# top_board.net
KiCad netlist of a schematic drawn in EAGLE
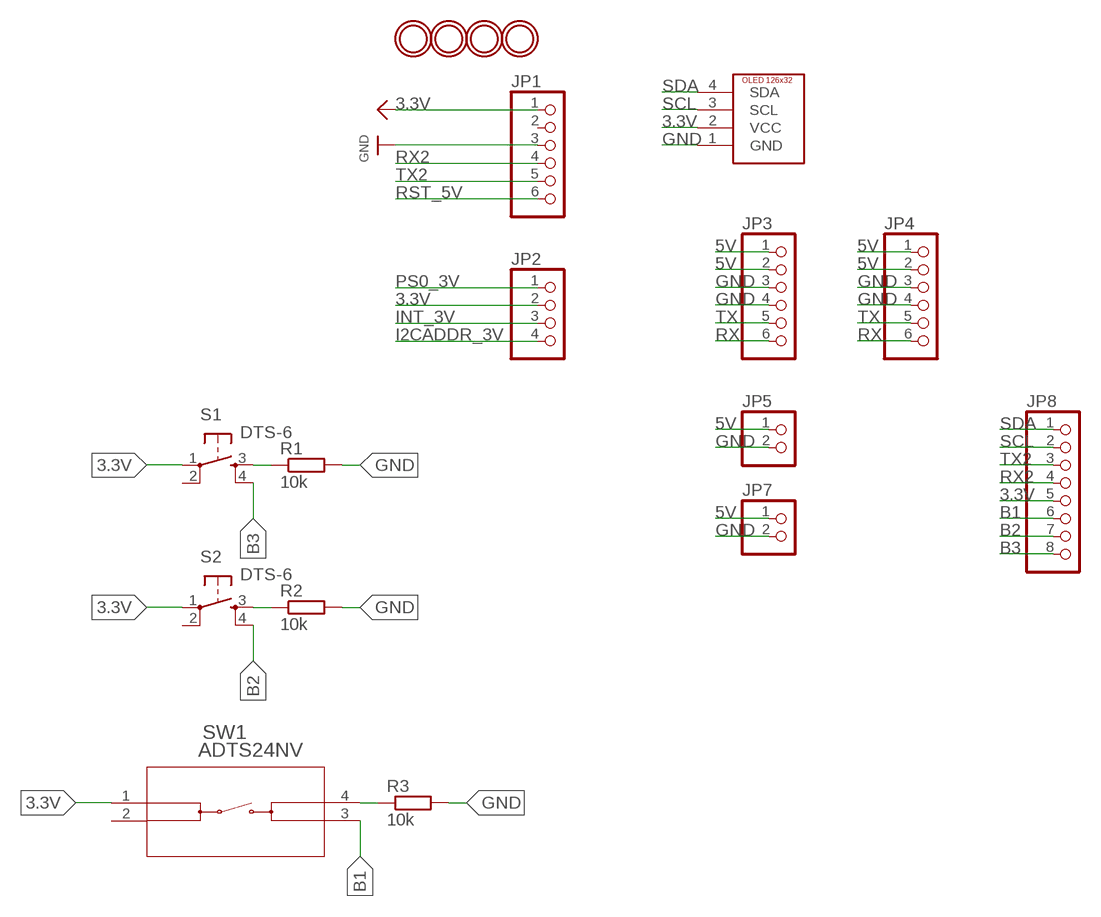
[diagram p0: schematic, sheet 1]

(export (version "E")
  (design (tool "Eeschema 10.0.6"))
  (components
    (comp (ref "JP1")
      (value "HEADER-1X676MIL")
      (footprint "eagle-import:1X06_ROUND_76")
      (libsource (lib "eagle-import") (part "HEADER-1X676MIL"))
    )
    (comp (ref "JP2")
      (value "HEADER-1X476MIL")
      (footprint "eagle-import:1X04_ROUND_76")
      (libsource (lib "eagle-import") (part "HEADER-1X476MIL"))
    )
    (comp (ref "JP3")
      (value "PINHD-1X6")
      (footprint "eagle-import:1X06")
      (libsource (lib "eagle-import") (part "PINHD-1X6"))
    )
    (comp (ref "JP4")
      (value "PINHD-1X6")
      (footprint "eagle-import:1X06")
      (libsource (lib "eagle-import") (part "PINHD-1X6"))
    )
    (comp (ref "JP5")
      (value "PINHD-1X2")
      (footprint "eagle-import:1X02")
      (libsource (lib "eagle-import") (part "PINHD-1X2"))
    )
    (comp (ref "JP7")
      (value "PINHD-1X2")
      (footprint "eagle-import:1X02")
      (libsource (lib "eagle-import") (part "PINHD-1X2"))
    )
    (comp (ref "JP8")
      (value "PINHD-1X8")
      (footprint "eagle-import:1X08")
      (libsource (lib "eagle-import") (part "PINHD-1X8"))
    )
    (comp (ref "R1")
      (value "10k")
      (footprint "eagle-import:R0603")
      (libsource (lib "eagle-import") (part "R-EU_R0603"))
    )
    (comp (ref "R2")
      (value "10k")
      (footprint "eagle-import:R0603")
      (libsource (lib "eagle-import") (part "R-EU_R0603"))
    )
    (comp (ref "R3")
      (value "10k")
      (footprint "eagle-import:R0603")
      (libsource (lib "eagle-import") (part "R-EU_R0603"))
    )
    (comp (ref "S1")
      (value "DTS-6")
      (footprint "eagle-import:DTS-6")
      (libsource (lib "eagle-import") (part "DTS-6"))
    )
    (comp (ref "S2")
      (value "DTS-6")
      (footprint "eagle-import:DTS-6")
      (libsource (lib "eagle-import") (part "DTS-6"))
    )
    (comp (ref "SW1")
      (value "ADTS24NV")
      (footprint "eagle-import:ADTS24_V_APM")
      (fields (field (name "COPYRIGHT") "Copyright (C) 2023 Ultra Librarian. All rights reserved."))
      (libsource (lib "eagle-import") (part "ADTS24NV"))
    )
    (comp (ref "U$1")
      (value "OLED126X32THROUGH_HOLE")
      (footprint "eagle-import:OLED128X64")
      (libsource (lib "eagle-import") (part "OLED126X32THROUGH_HOLE"))
    )
    (comp (ref "U$29")
      (value "MOUNTINGHOLE2.5_THICK")
      (footprint "eagle-import:MOUNTINGHOLE_2.5_PLATED_THICK")
      (libsource (lib "eagle-import") (part "MOUNTINGHOLE2.5_THICK"))
    )
    (comp (ref "U$30")
      (value "MOUNTINGHOLE2.5_THICK")
      (footprint "eagle-import:MOUNTINGHOLE_2.5_PLATED_THICK")
      (libsource (lib "eagle-import") (part "MOUNTINGHOLE2.5_THICK"))
    )
    (comp (ref "U$31")
      (value "MOUNTINGHOLE2.5_THICK")
      (footprint "eagle-import:MOUNTINGHOLE_2.5_PLATED_THICK")
      (libsource (lib "eagle-import") (part "MOUNTINGHOLE2.5_THICK"))
    )
    (comp (ref "U$32")
      (value "MOUNTINGHOLE2.5_THICK")
      (footprint "eagle-import:MOUNTINGHOLE_2.5_PLATED_THICK")
      (libsource (lib "eagle-import") (part "MOUNTINGHOLE2.5_THICK"))
    )
  )
  (nets
    (net (code "1") (name "/5V") (class "Default")
      (node (ref "JP3") (pin "1") (pinfunction "1_1") (pintype "passive"))
      (node (ref "JP3") (pin "2") (pinfunction "2_2") (pintype "passive"))
      (node (ref "JP4") (pin "1") (pinfunction "1_1") (pintype "passive"))
      (node (ref "JP4") (pin "2") (pinfunction "2_2") (pintype "passive"))
      (node (ref "JP5") (pin "1") (pinfunction "1_1") (pintype "passive"))
      (node (ref "JP7") (pin "1") (pinfunction "1_1") (pintype "passive"))
    )
    (net (code "2") (name "/I2CADDR_3V") (class "Default")
      (node (ref "JP2") (pin "4") (pinfunction "4_4") (pintype "passive"))
    )
    (net (code "3") (name "/INT_3V") (class "Default")
      (node (ref "JP2") (pin "3") (pinfunction "3_3") (pintype "passive"))
    )
    (net (code "4") (name "/PS0_3V") (class "Default")
      (node (ref "JP2") (pin "1") (pinfunction "1_1") (pintype "passive"))
    )
    (net (code "5") (name "/RST_5V") (class "Default")
      (node (ref "JP1") (pin "6") (pinfunction "6_6") (pintype "passive"))
    )
    (net (code "6") (name "/RX") (class "Default")
      (node (ref "JP3") (pin "6") (pinfunction "6_6") (pintype "passive"))
      (node (ref "JP4") (pin "6") (pinfunction "6_6") (pintype "passive"))
    )
    (net (code "7") (name "/RX2") (class "Default")
      (node (ref "JP1") (pin "4") (pinfunction "4_4") (pintype "passive"))
      (node (ref "JP8") (pin "4") (pinfunction "4_4") (pintype "passive"))
    )
    (net (code "8") (name "/SCL") (class "Default")
      (node (ref "JP8") (pin "2") (pinfunction "2_2") (pintype "passive"))
      (node (ref "U$1") (pin "3") (pinfunction "SCL_3") (pintype "bidirectional"))
    )
    (net (code "9") (name "/SDA") (class "Default")
      (node (ref "JP8") (pin "1") (pinfunction "1_1") (pintype "passive"))
      (node (ref "U$1") (pin "4") (pinfunction "SDA_4") (pintype "bidirectional"))
    )
    (net (code "10") (name "/TX") (class "Default")
      (node (ref "JP3") (pin "5") (pinfunction "5_5") (pintype "passive"))
      (node (ref "JP4") (pin "5") (pinfunction "5_5") (pintype "passive"))
    )
    (net (code "11") (name "/TX2") (class "Default")
      (node (ref "JP1") (pin "5") (pinfunction "5_5") (pintype "passive"))
      (node (ref "JP8") (pin "3") (pinfunction "3_3") (pintype "passive"))
    )
    (net (code "12") (name "3.3V") (class "Default")
      (node (ref "JP1") (pin "1") (pinfunction "1_1") (pintype "passive"))
      (node (ref "JP2") (pin "2") (pinfunction "2_2") (pintype "passive"))
      (node (ref "JP8") (pin "5") (pinfunction "5_5") (pintype "passive"))
      (node (ref "S1") (pin "1") (pinfunction "1_1") (pintype "passive"))
      (node (ref "S2") (pin "1") (pinfunction "1_1") (pintype "passive"))
      (node (ref "SW1") (pin "1") (pinfunction "1_1") (pintype "passive"))
      (node (ref "U$1") (pin "2") (pinfunction "VCC_2") (pintype "bidirectional"))
    )
    (net (code "13") (name "B1") (class "Default")
      (node (ref "JP8") (pin "6") (pinfunction "6_6") (pintype "passive"))
      (node (ref "SW1") (pin "3") (pinfunction "3_3") (pintype "passive"))
    )
    (net (code "14") (name "B2") (class "Default")
      (node (ref "JP8") (pin "7") (pinfunction "7_7") (pintype "passive"))
      (node (ref "S2") (pin "4") (pinfunction "4_4") (pintype "passive"))
    )
    (net (code "15") (name "B3") (class "Default")
      (node (ref "JP8") (pin "8") (pinfunction "8_8") (pintype "passive"))
      (node (ref "S1") (pin "4") (pinfunction "4_4") (pintype "passive"))
    )
    (net (code "16") (name "GND") (class "Default")
      (node (ref "JP1") (pin "3") (pinfunction "3_3") (pintype "passive"))
      (node (ref "JP3") (pin "3") (pinfunction "3_3") (pintype "passive"))
      (node (ref "JP3") (pin "4") (pinfunction "4_4") (pintype "passive"))
      (node (ref "JP4") (pin "3") (pinfunction "3_3") (pintype "passive"))
      (node (ref "JP4") (pin "4") (pinfunction "4_4") (pintype "passive"))
      (node (ref "JP5") (pin "2") (pinfunction "2_2") (pintype "passive"))
      (node (ref "JP7") (pin "2") (pinfunction "2_2") (pintype "passive"))
      (node (ref "R1") (pin "2") (pinfunction "2_2") (pintype "passive"))
      (node (ref "R2") (pin "2") (pinfunction "2_2") (pintype "passive"))
      (node (ref "R3") (pin "2") (pinfunction "2_2") (pintype "passive"))
      (node (ref "U$1") (pin "1") (pinfunction "GND_1") (pintype "bidirectional"))
    )
    (net (code "17") (name "Net-(R1-Pad1)") (class "Default")
      (node (ref "R1") (pin "1") (pinfunction "1_1") (pintype "passive"))
      (node (ref "S1") (pin "3") (pinfunction "3_3") (pintype "passive"))
    )
    (net (code "18") (name "Net-(R2-Pad1)") (class "Default")
      (node (ref "R2") (pin "1") (pinfunction "1_1") (pintype "passive"))
      (node (ref "S2") (pin "3") (pinfunction "3_3") (pintype "passive"))
    )
    (net (code "19") (name "Net-(R3-Pad1)") (class "Default")
      (node (ref "R3") (pin "1") (pinfunction "1_1") (pintype "passive"))
      (node (ref "SW1") (pin "4") (pinfunction "4_4") (pintype "passive"))
    )
    (net (code "20") (name "unconnected-(JP1-Pad2)") (class "Default")
      (node (ref "JP1") (pin "2") (pinfunction "2_2") (pintype "passive"))
    )
    (net (code "21") (name "unconnected-(S1-Pad2)") (class "Default")
      (node (ref "S1") (pin "2") (pinfunction "2_2") (pintype "passive"))
    )
    (net (code "22") (name "unconnected-(S2-Pad2)") (class "Default")
      (node (ref "S2") (pin "2") (pinfunction "2_2") (pintype "passive"))
    )
    (net (code "23") (name "unconnected-(SW1-Pad2)") (class "Default")
      (node (ref "SW1") (pin "2") (pinfunction "2_2") (pintype "passive"))
    )
  )
)
